# schema_puissance.net
KiCad netlist of a schematic drawn in EAGLE
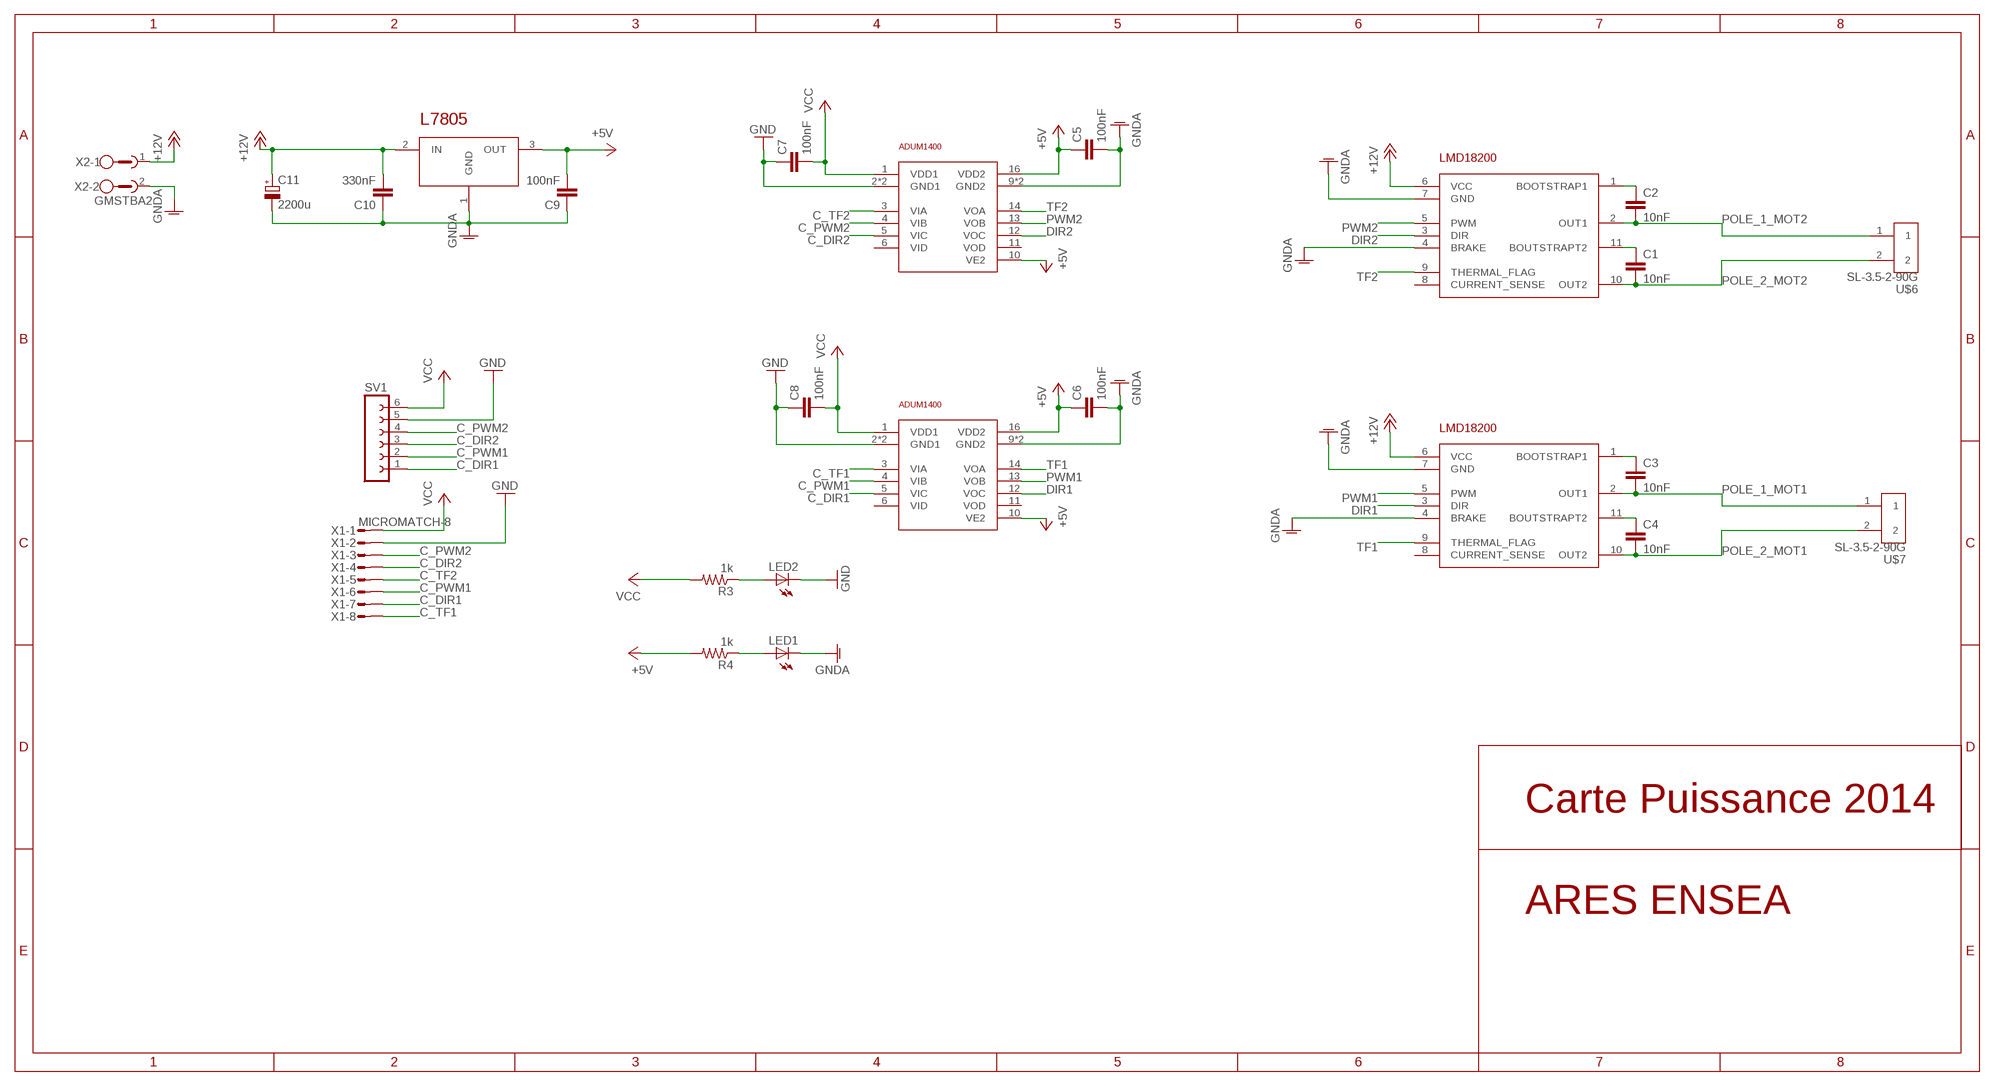
[diagram p0: schematic, sheet 1]

(export (version "E")
  (design (tool "Eeschema 10.0.6"))
  (components
    (comp (ref "C1")
      (value "10nF")
      (footprint "eagle-import:C0805")
      (libsource (lib "eagle-import") (part "C-EUC0805"))
    )
    (comp (ref "C2")
      (value "10nF")
      (footprint "eagle-import:C0805")
      (libsource (lib "eagle-import") (part "C-EUC0805"))
    )
    (comp (ref "C3")
      (value "10nF")
      (footprint "eagle-import:C0805")
      (libsource (lib "eagle-import") (part "C-EUC0805"))
    )
    (comp (ref "C4")
      (value "10nF")
      (footprint "eagle-import:C0805")
      (libsource (lib "eagle-import") (part "C-EUC0805"))
    )
    (comp (ref "C5")
      (value "100nF")
      (footprint "eagle-import:C0805")
      (libsource (lib "eagle-import") (part "C-EUC0805"))
    )
    (comp (ref "C6")
      (value "100nF")
      (footprint "eagle-import:C0805")
      (libsource (lib "eagle-import") (part "C-EUC0805"))
    )
    (comp (ref "C7")
      (value "100nF")
      (footprint "eagle-import:C0805")
      (libsource (lib "eagle-import") (part "C-EUC0805"))
    )
    (comp (ref "C8")
      (value "100nF")
      (footprint "eagle-import:C0805")
      (libsource (lib "eagle-import") (part "C-EUC0805"))
    )
    (comp (ref "C9")
      (value "100nF")
      (footprint "eagle-import:C0805")
      (libsource (lib "eagle-import") (part "C-EUC0805"))
    )
    (comp (ref "C10")
      (value "330nF")
      (footprint "eagle-import:C0805")
      (libsource (lib "eagle-import") (part "C-EUC0805"))
    )
    (comp (ref "C11")
      (value "2200u")
      (footprint "eagle-import:TT5D11")
      (libsource (lib "eagle-import") (part "CPOL-EUTT5D11"))
    )
    (comp (ref "LED1")
      (value "LEDSML0805")
      (footprint "eagle-import:SML0805")
      (libsource (lib "eagle-import") (part "LEDSML0805"))
    )
    (comp (ref "LED2")
      (value "LEDSML0805")
      (footprint "eagle-import:SML0805")
      (libsource (lib "eagle-import") (part "LEDSML0805"))
    )
    (comp (ref "R3")
      (value "1k")
      (footprint "eagle-import:M0805")
      (libsource (lib "eagle-import") (part "R-US_M0805"))
    )
    (comp (ref "R4")
      (value "1k")
      (footprint "eagle-import:M0805")
      (libsource (lib "eagle-import") (part "R-US_M0805"))
    )
    (comp (ref "SV1")
      (value "FE06-1")
      (footprint "eagle-import:FE06")
      (libsource (lib "eagle-import") (part "FE06-1"))
    )
    (comp (ref "U$1")
      (value "LMD18200")
      (footprint "eagle-import:LMD18200")
      (libsource (lib "eagle-import") (part "LMD18200"))
    )
    (comp (ref "U$2")
      (value "LMD18200")
      (footprint "eagle-import:LMD18200")
      (libsource (lib "eagle-import") (part "LMD18200"))
    )
    (comp (ref "U$3")
      (value "ADUM1400S")
      (footprint "eagle-import:SO-16W")
      (libsource (lib "eagle-import") (part "ADUM1400S"))
    )
    (comp (ref "U$4")
      (value "ADUM1400S")
      (footprint "eagle-import:SO-16W")
      (libsource (lib "eagle-import") (part "ADUM1400S"))
    )
    (comp (ref "U$5")
      (value "L7805TO263")
      (footprint "eagle-import:DPAK")
      (libsource (lib "eagle-import") (part "L7805TO263"))
    )
    (comp (ref "U$6")
      (value "SL-3.5-2-90G")
      (footprint "eagle-import:SL-3.5-2-90G")
      (libsource (lib "eagle-import") (part "SL-3.5-2-90G"))
    )
    (comp (ref "U$7")
      (value "SL-3.5-2-90G")
      (footprint "eagle-import:SL-3.5-2-90G")
      (libsource (lib "eagle-import") (part "SL-3.5-2-90G"))
    )
    (comp (ref "X1")
      (value "MICROMATCH-8")
      (footprint "eagle-import:MICROMATCH-8")
      (fields (field (name "MF") "FARNELL") (field (name "MPN") "7-215464-8"))
      (libsource (lib "eagle-import") (part "MICROMATCH-8"))
    )
    (comp (ref "X2")
      (value "GMSTBA2")
      (footprint "eagle-import:GMSTBA2")
      (fields (field (name "MF") "FARNELL") (field (name "MPN") "1757242"))
      (libsource (lib "eagle-import") (part "GMSTBA2"))
    )
  )
  (nets
    (net (code "1") (name "+5V") (class "Default")
      (node (ref "C5") (pin "1") (pinfunction "1_1") (pintype "passive"))
      (node (ref "C6") (pin "1") (pinfunction "1_1") (pintype "passive"))
      (node (ref "C9") (pin "2") (pinfunction "2_2") (pintype "passive"))
      (node (ref "R4") (pin "2") (pinfunction "2_2") (pintype "passive"))
      (node (ref "U$3") (pin "10") (pinfunction "VE2_10") (pintype "bidirectional"))
      (node (ref "U$3") (pin "16") (pinfunction "VDD2_16") (pintype "bidirectional"))
      (node (ref "U$4") (pin "10") (pinfunction "VE2_10") (pintype "bidirectional"))
      (node (ref "U$4") (pin "16") (pinfunction "VDD2_16") (pintype "bidirectional"))
      (node (ref "U$5") (pin "3") (pinfunction "OUT_3") (pintype "bidirectional"))
    )
    (net (code "2") (name "+12V") (class "Default")
      (node (ref "C10") (pin "2") (pinfunction "2_2") (pintype "passive"))
      (node (ref "C11") (pin "+") (pinfunction "+_+") (pintype "passive"))
      (node (ref "U$1") (pin "6") (pinfunction "VCC_6") (pintype "bidirectional"))
      (node (ref "U$2") (pin "6") (pinfunction "VCC_6") (pintype "bidirectional"))
      (node (ref "U$5") (pin "2") (pinfunction "IN_2") (pintype "bidirectional"))
      (node (ref "X2") (pin "1") (pinfunction "1_1") (pintype "passive"))
    )
    (net (code "3") (name "/C_DIR1") (class "Default")
      (node (ref "SV1") (pin "1") (pinfunction "1_1") (pintype "passive"))
      (node (ref "U$4") (pin "5") (pinfunction "VIC_5") (pintype "bidirectional"))
      (node (ref "X1") (pin "7") (pinfunction "S_7") (pintype "passive"))
    )
    (net (code "4") (name "/C_DIR2") (class "Default")
      (node (ref "SV1") (pin "3") (pinfunction "3_3") (pintype "passive"))
      (node (ref "U$3") (pin "5") (pinfunction "VIC_5") (pintype "bidirectional"))
      (node (ref "X1") (pin "4") (pinfunction "S_4") (pintype "passive"))
    )
    (net (code "5") (name "/C_PWM1") (class "Default")
      (node (ref "SV1") (pin "2") (pinfunction "2_2") (pintype "passive"))
      (node (ref "U$4") (pin "4") (pinfunction "VIB_4") (pintype "bidirectional"))
      (node (ref "X1") (pin "6") (pinfunction "S_6") (pintype "passive"))
    )
    (net (code "6") (name "/C_PWM2") (class "Default")
      (node (ref "SV1") (pin "4") (pinfunction "4_4") (pintype "passive"))
      (node (ref "U$3") (pin "4") (pinfunction "VIB_4") (pintype "bidirectional"))
      (node (ref "X1") (pin "3") (pinfunction "S_3") (pintype "passive"))
    )
    (net (code "7") (name "/C_TF1") (class "Default")
      (node (ref "U$4") (pin "3") (pinfunction "VIA_3") (pintype "bidirectional"))
      (node (ref "X1") (pin "8") (pinfunction "S_8") (pintype "passive"))
    )
    (net (code "8") (name "/C_TF2") (class "Default")
      (node (ref "U$3") (pin "3") (pinfunction "VIA_3") (pintype "bidirectional"))
      (node (ref "X1") (pin "5") (pinfunction "S_5") (pintype "passive"))
    )
    (net (code "9") (name "/DIR1") (class "Default")
      (node (ref "U$1") (pin "3") (pinfunction "DIR_3") (pintype "bidirectional"))
      (node (ref "U$4") (pin "12") (pinfunction "VOC_12") (pintype "bidirectional"))
    )
    (net (code "10") (name "/DIR2") (class "Default")
      (node (ref "U$2") (pin "3") (pinfunction "DIR_3") (pintype "bidirectional"))
      (node (ref "U$3") (pin "12") (pinfunction "VOC_12") (pintype "bidirectional"))
    )
    (net (code "11") (name "/POLE_1_MOT1") (class "Default")
      (node (ref "C3") (pin "2") (pinfunction "2_2") (pintype "passive"))
      (node (ref "U$1") (pin "2") (pinfunction "OUT1_2") (pintype "bidirectional"))
      (node (ref "U$7") (pin "1") (pinfunction "1_1") (pintype "bidirectional"))
    )
    (net (code "12") (name "/POLE_1_MOT2") (class "Default")
      (node (ref "C2") (pin "2") (pinfunction "2_2") (pintype "passive"))
      (node (ref "U$2") (pin "2") (pinfunction "OUT1_2") (pintype "bidirectional"))
      (node (ref "U$6") (pin "1") (pinfunction "1_1") (pintype "bidirectional"))
    )
    (net (code "13") (name "/POLE_2_MOT1") (class "Default")
      (node (ref "C4") (pin "2") (pinfunction "2_2") (pintype "passive"))
      (node (ref "U$1") (pin "10") (pinfunction "OUT2_10") (pintype "bidirectional"))
      (node (ref "U$7") (pin "2") (pinfunction "2_2") (pintype "bidirectional"))
    )
    (net (code "14") (name "/POLE_2_MOT2") (class "Default")
      (node (ref "C1") (pin "2") (pinfunction "2_2") (pintype "passive"))
      (node (ref "U$2") (pin "10") (pinfunction "OUT2_10") (pintype "bidirectional"))
      (node (ref "U$6") (pin "2") (pinfunction "2_2") (pintype "bidirectional"))
    )
    (net (code "15") (name "/PWM1") (class "Default")
      (node (ref "U$1") (pin "5") (pinfunction "PWM_5") (pintype "bidirectional"))
      (node (ref "U$4") (pin "13") (pinfunction "VOB_13") (pintype "bidirectional"))
    )
    (net (code "16") (name "/PWM2") (class "Default")
      (node (ref "U$2") (pin "5") (pinfunction "PWM_5") (pintype "bidirectional"))
      (node (ref "U$3") (pin "13") (pinfunction "VOB_13") (pintype "bidirectional"))
    )
    (net (code "17") (name "/TF1") (class "Default")
      (node (ref "U$1") (pin "9") (pinfunction "THERMAL_FLAG_9") (pintype "bidirectional"))
      (node (ref "U$4") (pin "14") (pinfunction "VOA_14") (pintype "bidirectional"))
    )
    (net (code "18") (name "/TF2") (class "Default")
      (node (ref "U$2") (pin "9") (pinfunction "THERMAL_FLAG_9") (pintype "bidirectional"))
      (node (ref "U$3") (pin "14") (pinfunction "VOA_14") (pintype "bidirectional"))
    )
    (net (code "19") (name "GND") (class "Default")
      (node (ref "C7") (pin "1") (pinfunction "1_1") (pintype "passive"))
      (node (ref "C8") (pin "1") (pinfunction "1_1") (pintype "passive"))
      (node (ref "LED2") (pin "C") (pinfunction "C_C") (pintype "passive"))
      (node (ref "SV1") (pin "5") (pinfunction "5_5") (pintype "passive"))
      (node (ref "U$3") (pin "2") (pinfunction "GND1_2") (pintype "bidirectional"))
      (node (ref "U$3") (pin "8") (pinfunction "GND1_8") (pintype "bidirectional"))
      (node (ref "U$4") (pin "2") (pinfunction "GND1_2") (pintype "bidirectional"))
      (node (ref "U$4") (pin "8") (pinfunction "GND1_8") (pintype "bidirectional"))
      (node (ref "X1") (pin "2") (pinfunction "S_2") (pintype "passive"))
    )
    (net (code "20") (name "GNDA") (class "Default")
      (node (ref "C10") (pin "1") (pinfunction "1_1") (pintype "passive"))
      (node (ref "C11") (pin "-") (pinfunction "-_-") (pintype "passive"))
      (node (ref "C5") (pin "2") (pinfunction "2_2") (pintype "passive"))
      (node (ref "C6") (pin "2") (pinfunction "2_2") (pintype "passive"))
      (node (ref "C9") (pin "1") (pinfunction "1_1") (pintype "passive"))
      (node (ref "LED1") (pin "C") (pinfunction "C_C") (pintype "passive"))
      (node (ref "U$1") (pin "4") (pinfunction "BRAKE_4") (pintype "bidirectional"))
      (node (ref "U$1") (pin "7") (pinfunction "GND_7") (pintype "bidirectional"))
      (node (ref "U$2") (pin "4") (pinfunction "BRAKE_4") (pintype "bidirectional"))
      (node (ref "U$2") (pin "7") (pinfunction "GND_7") (pintype "bidirectional"))
      (node (ref "U$3") (pin "15") (pinfunction "GND2_15") (pintype "bidirectional"))
      (node (ref "U$3") (pin "9") (pinfunction "GND2_9") (pintype "bidirectional"))
      (node (ref "U$4") (pin "15") (pinfunction "GND2_15") (pintype "bidirectional"))
      (node (ref "U$4") (pin "9") (pinfunction "GND2_9") (pintype "bidirectional"))
      (node (ref "U$5") (pin "1") (pinfunction "GND_1") (pintype "bidirectional"))
      (node (ref "X2") (pin "2") (pinfunction "1_2") (pintype "passive"))
    )
    (net (code "21") (name "Net-(LED1-PadA)") (class "Default")
      (node (ref "LED1") (pin "A") (pinfunction "A_A") (pintype "passive"))
      (node (ref "R4") (pin "1") (pinfunction "1_1") (pintype "passive"))
    )
    (net (code "22") (name "Net-(LED2-PadA)") (class "Default")
      (node (ref "LED2") (pin "A") (pinfunction "A_A") (pintype "passive"))
      (node (ref "R3") (pin "1") (pinfunction "1_1") (pintype "passive"))
    )
    (net (code "23") (name "Net-(U$1-BOOTSTRAP1)") (class "Default")
      (node (ref "C3") (pin "1") (pinfunction "1_1") (pintype "passive"))
      (node (ref "U$1") (pin "1") (pinfunction "BOOTSTRAP1_1") (pintype "bidirectional"))
    )
    (net (code "24") (name "Net-(U$1-BOUTSTRAPT2)") (class "Default")
      (node (ref "C4") (pin "1") (pinfunction "1_1") (pintype "passive"))
      (node (ref "U$1") (pin "11") (pinfunction "BOUTSTRAPT2_11") (pintype "bidirectional"))
    )
    (net (code "25") (name "Net-(U$2-BOOTSTRAP1)") (class "Default")
      (node (ref "C2") (pin "1") (pinfunction "1_1") (pintype "passive"))
      (node (ref "U$2") (pin "1") (pinfunction "BOOTSTRAP1_1") (pintype "bidirectional"))
    )
    (net (code "26") (name "Net-(U$2-BOUTSTRAPT2)") (class "Default")
      (node (ref "C1") (pin "1") (pinfunction "1_1") (pintype "passive"))
      (node (ref "U$2") (pin "11") (pinfunction "BOUTSTRAPT2_11") (pintype "bidirectional"))
    )
    (net (code "27") (name "VCC") (class "Default")
      (node (ref "C7") (pin "2") (pinfunction "2_2") (pintype "passive"))
      (node (ref "C8") (pin "2") (pinfunction "2_2") (pintype "passive"))
      (node (ref "R3") (pin "2") (pinfunction "2_2") (pintype "passive"))
      (node (ref "SV1") (pin "6") (pinfunction "6_6") (pintype "passive"))
      (node (ref "U$3") (pin "1") (pinfunction "VDD1_1") (pintype "bidirectional"))
      (node (ref "U$4") (pin "1") (pinfunction "VDD1_1") (pintype "bidirectional"))
      (node (ref "X1") (pin "1") (pinfunction "S_1") (pintype "passive"))
    )
    (net (code "28") (name "unconnected-(U$1-CURRENT_SENSE-Pad8)") (class "Default")
      (node (ref "U$1") (pin "8") (pinfunction "CURRENT_SENSE_8") (pintype "bidirectional"))
    )
    (net (code "29") (name "unconnected-(U$2-CURRENT_SENSE-Pad8)") (class "Default")
      (node (ref "U$2") (pin "8") (pinfunction "CURRENT_SENSE_8") (pintype "bidirectional"))
    )
    (net (code "30") (name "unconnected-(U$3-VID-Pad6)") (class "Default")
      (node (ref "U$3") (pin "6") (pinfunction "VID_6") (pintype "bidirectional"))
    )
    (net (code "31") (name "unconnected-(U$3-VOD-Pad11)") (class "Default")
      (node (ref "U$3") (pin "11") (pinfunction "VOD_11") (pintype "bidirectional"))
    )
    (net (code "32") (name "unconnected-(U$4-VID-Pad6)") (class "Default")
      (node (ref "U$4") (pin "6") (pinfunction "VID_6") (pintype "bidirectional"))
    )
    (net (code "33") (name "unconnected-(U$4-VOD-Pad11)") (class "Default")
      (node (ref "U$4") (pin "11") (pinfunction "VOD_11") (pintype "bidirectional"))
    )
  )
)
